# Works_009_a.net
KiCad netlist of a schematic drawn in EAGLE
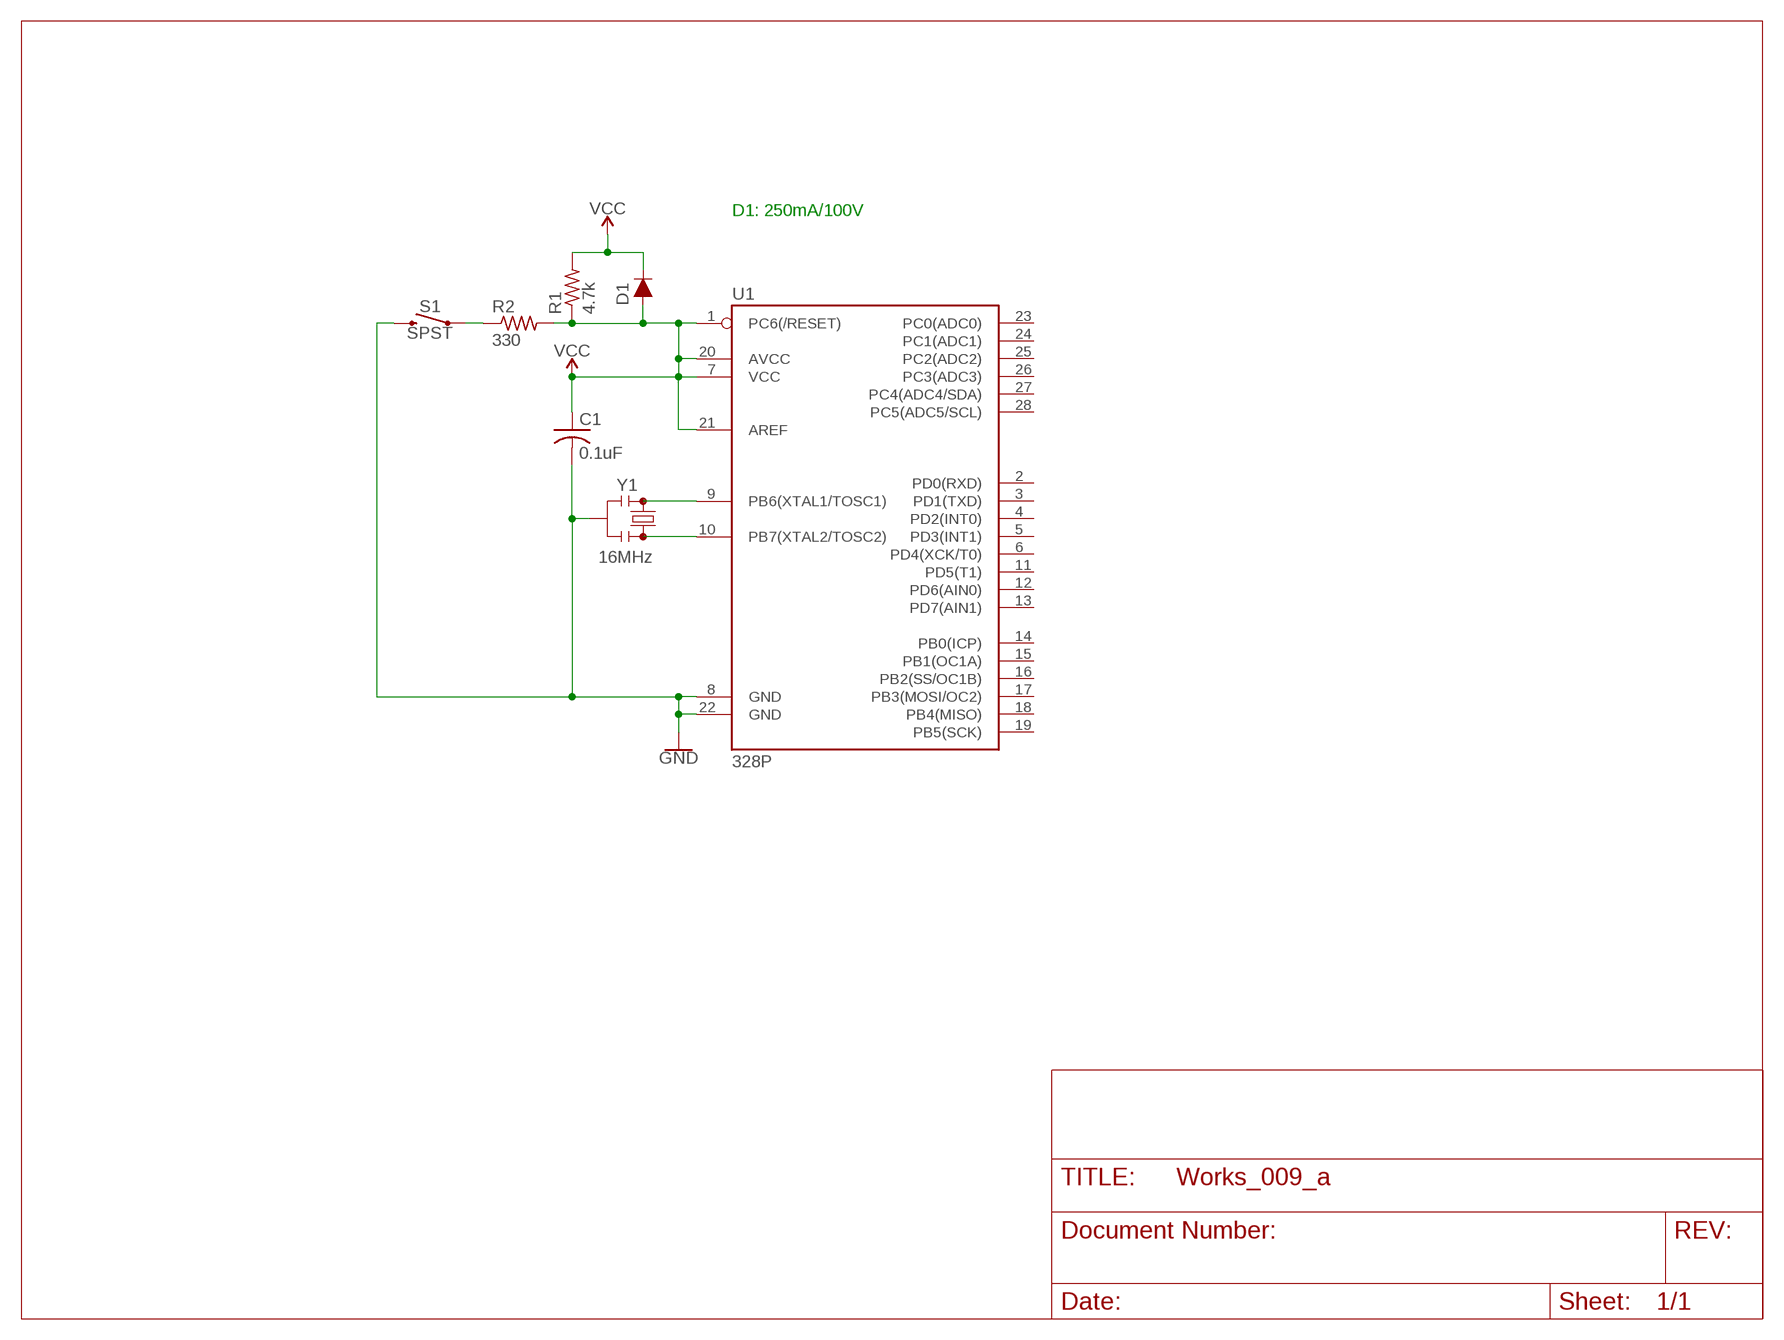
[diagram p0: schematic, sheet 1]

(export (version "E")
  (design (tool "Eeschema 10.0.6"))
  (components
    (comp (ref "C1")
      (value "0.1uF")
      (footprint "eagle-import:C0805")
      (libsource (lib "eagle-import") (part "C-USC0805"))
    )
    (comp (ref "D1")
      (value "DIODE-BAS16J")
      (footprint "eagle-import:SOD-323")
      (libsource (lib "eagle-import") (part "DIODE-BAS16J"))
    )
    (comp (ref "R1")
      (value "4.7k")
      (footprint "eagle-import:R0805")
      (libsource (lib "eagle-import") (part "R-US_R0805"))
    )
    (comp (ref "R2")
      (value "330")
      (footprint "eagle-import:R0805")
      (libsource (lib "eagle-import") (part "R-US_R0805"))
    )
    (comp (ref "S1")
      (value "SPST")
      (footprint "eagle-import:TACTILE_SWITCH_SMD_5.2MM")
      (libsource (lib "eagle-import") (part "MOMENTARY-SWITCH-SPST-SMD-5.2MM"))
    )
    (comp (ref "U1")
      (value "328P")
      (footprint "eagle-import:DIP28")
      (libsource (lib "eagle-import") (part "ATMEGA328P_PDIP"))
    )
    (comp (ref "Y1")
      (value "16MHz")
      (footprint "eagle-import:RESONATOR-SMD-3.2X1.3")
      (libsource (lib "eagle-import") (part "RESONATOR-16MHZSMD_3.2X1.3"))
    )
  )
  (nets
    (net (code "1") (name "GND") (class "Default")
      (node (ref "C1") (pin "2") (pinfunction "2_2") (pintype "passive"))
      (node (ref "S1") (pin "3") (pinfunction "2_3") (pintype "passive"))
      (node (ref "U1") (pin "22") (pinfunction "GND_22") (pintype "bidirectional"))
      (node (ref "U1") (pin "8") (pinfunction "GND_8") (pintype "bidirectional"))
      (node (ref "Y1") (pin "2") (pinfunction "2_2") (pintype "passive"))
    )
    (net (code "2") (name "Net-(R2-Pad1)") (class "Default")
      (node (ref "R2") (pin "1") (pinfunction "1_1") (pintype "passive"))
      (node (ref "S1") (pin "1") (pinfunction "1_1") (pintype "passive"))
    )
    (net (code "3") (name "Net-(U1-PB6(XTAL1{slash}TOSC1))") (class "Default")
      (node (ref "U1") (pin "9") (pinfunction "PB6(XTAL1/TOSC1)_9") (pintype "bidirectional"))
      (node (ref "Y1") (pin "1") (pinfunction "1_1") (pintype "passive"))
    )
    (net (code "4") (name "Net-(U1-PB7(XTAL2{slash}TOSC2))") (class "Default")
      (node (ref "U1") (pin "10") (pinfunction "PB7(XTAL2/TOSC2)_10") (pintype "bidirectional"))
      (node (ref "Y1") (pin "3") (pinfunction "3_3") (pintype "passive"))
    )
    (net (code "5") (name "VCC") (class "Default")
      (node (ref "C1") (pin "1") (pinfunction "1_1") (pintype "passive"))
      (node (ref "D1") (pin "A") (pinfunction "A_A") (pintype "passive"))
      (node (ref "D1") (pin "C") (pinfunction "C_C") (pintype "passive"))
      (node (ref "R1") (pin "1") (pinfunction "1_1") (pintype "passive"))
      (node (ref "R1") (pin "2") (pinfunction "2_2") (pintype "passive"))
      (node (ref "R2") (pin "2") (pinfunction "2_2") (pintype "passive"))
      (node (ref "U1") (pin "1") (pinfunction "PC6(/RESET)_1") (pintype "bidirectional"))
      (node (ref "U1") (pin "20") (pinfunction "AVCC_20") (pintype "bidirectional"))
      (node (ref "U1") (pin "21") (pinfunction "AREF_21") (pintype "bidirectional"))
      (node (ref "U1") (pin "7") (pinfunction "VCC_7") (pintype "bidirectional"))
    )
    (net (code "6") (name "unconnected-(U1-PB0(ICP)-Pad14)") (class "Default")
      (node (ref "U1") (pin "14") (pinfunction "PB0(ICP)_14") (pintype "bidirectional"))
    )
    (net (code "7") (name "unconnected-(U1-PB1(OC1A)-Pad15)") (class "Default")
      (node (ref "U1") (pin "15") (pinfunction "PB1(OC1A)_15") (pintype "bidirectional"))
    )
    (net (code "8") (name "unconnected-(U1-PB2(SS{slash}OC1B)-Pad16)") (class "Default")
      (node (ref "U1") (pin "16") (pinfunction "PB2(SS/OC1B)_16") (pintype "bidirectional"))
    )
    (net (code "9") (name "unconnected-(U1-PB3(MOSI{slash}OC2)-Pad17)") (class "Default")
      (node (ref "U1") (pin "17") (pinfunction "PB3(MOSI/OC2)_17") (pintype "bidirectional"))
    )
    (net (code "10") (name "unconnected-(U1-PB4(MISO)-Pad18)") (class "Default")
      (node (ref "U1") (pin "18") (pinfunction "PB4(MISO)_18") (pintype "bidirectional"))
    )
    (net (code "11") (name "unconnected-(U1-PB5(SCK)-Pad19)") (class "Default")
      (node (ref "U1") (pin "19") (pinfunction "PB5(SCK)_19") (pintype "bidirectional"))
    )
    (net (code "12") (name "unconnected-(U1-PC0(ADC0)-Pad23)") (class "Default")
      (node (ref "U1") (pin "23") (pinfunction "PC0(ADC0)_23") (pintype "bidirectional"))
    )
    (net (code "13") (name "unconnected-(U1-PC1(ADC1)-Pad24)") (class "Default")
      (node (ref "U1") (pin "24") (pinfunction "PC1(ADC1)_24") (pintype "bidirectional"))
    )
    (net (code "14") (name "unconnected-(U1-PC2(ADC2)-Pad25)") (class "Default")
      (node (ref "U1") (pin "25") (pinfunction "PC2(ADC2)_25") (pintype "bidirectional"))
    )
    (net (code "15") (name "unconnected-(U1-PC3(ADC3)-Pad26)") (class "Default")
      (node (ref "U1") (pin "26") (pinfunction "PC3(ADC3)_26") (pintype "bidirectional"))
    )
    (net (code "16") (name "unconnected-(U1-PC4(ADC4{slash}SDA)-Pad27)") (class "Default")
      (node (ref "U1") (pin "27") (pinfunction "PC4(ADC4/SDA)_27") (pintype "bidirectional"))
    )
    (net (code "17") (name "unconnected-(U1-PC5(ADC5{slash}SCL)-Pad28)") (class "Default")
      (node (ref "U1") (pin "28") (pinfunction "PC5(ADC5/SCL)_28") (pintype "bidirectional"))
    )
    (net (code "18") (name "unconnected-(U1-PD0(RXD)-Pad2)") (class "Default")
      (node (ref "U1") (pin "2") (pinfunction "PD0(RXD)_2") (pintype "bidirectional"))
    )
    (net (code "19") (name "unconnected-(U1-PD1(TXD)-Pad3)") (class "Default")
      (node (ref "U1") (pin "3") (pinfunction "PD1(TXD)_3") (pintype "bidirectional"))
    )
    (net (code "20") (name "unconnected-(U1-PD2(INT0)-Pad4)") (class "Default")
      (node (ref "U1") (pin "4") (pinfunction "PD2(INT0)_4") (pintype "bidirectional"))
    )
    (net (code "21") (name "unconnected-(U1-PD3(INT1)-Pad5)") (class "Default")
      (node (ref "U1") (pin "5") (pinfunction "PD3(INT1)_5") (pintype "bidirectional"))
    )
    (net (code "22") (name "unconnected-(U1-PD4(XCK{slash}T0)-Pad6)") (class "Default")
      (node (ref "U1") (pin "6") (pinfunction "PD4(XCK/T0)_6") (pintype "bidirectional"))
    )
    (net (code "23") (name "unconnected-(U1-PD5(T1)-Pad11)") (class "Default")
      (node (ref "U1") (pin "11") (pinfunction "PD5(T1)_11") (pintype "bidirectional"))
    )
    (net (code "24") (name "unconnected-(U1-PD6(AIN0)-Pad12)") (class "Default")
      (node (ref "U1") (pin "12") (pinfunction "PD6(AIN0)_12") (pintype "bidirectional"))
    )
    (net (code "25") (name "unconnected-(U1-PD7(AIN1)-Pad13)") (class "Default")
      (node (ref "U1") (pin "13") (pinfunction "PD7(AIN1)_13") (pintype "bidirectional"))
    )
  )
)
